# LB_BIT_2IN_1OUT-LARGE-v03_1_1x.net
KiCad netlist of a schematic drawn in EAGLE
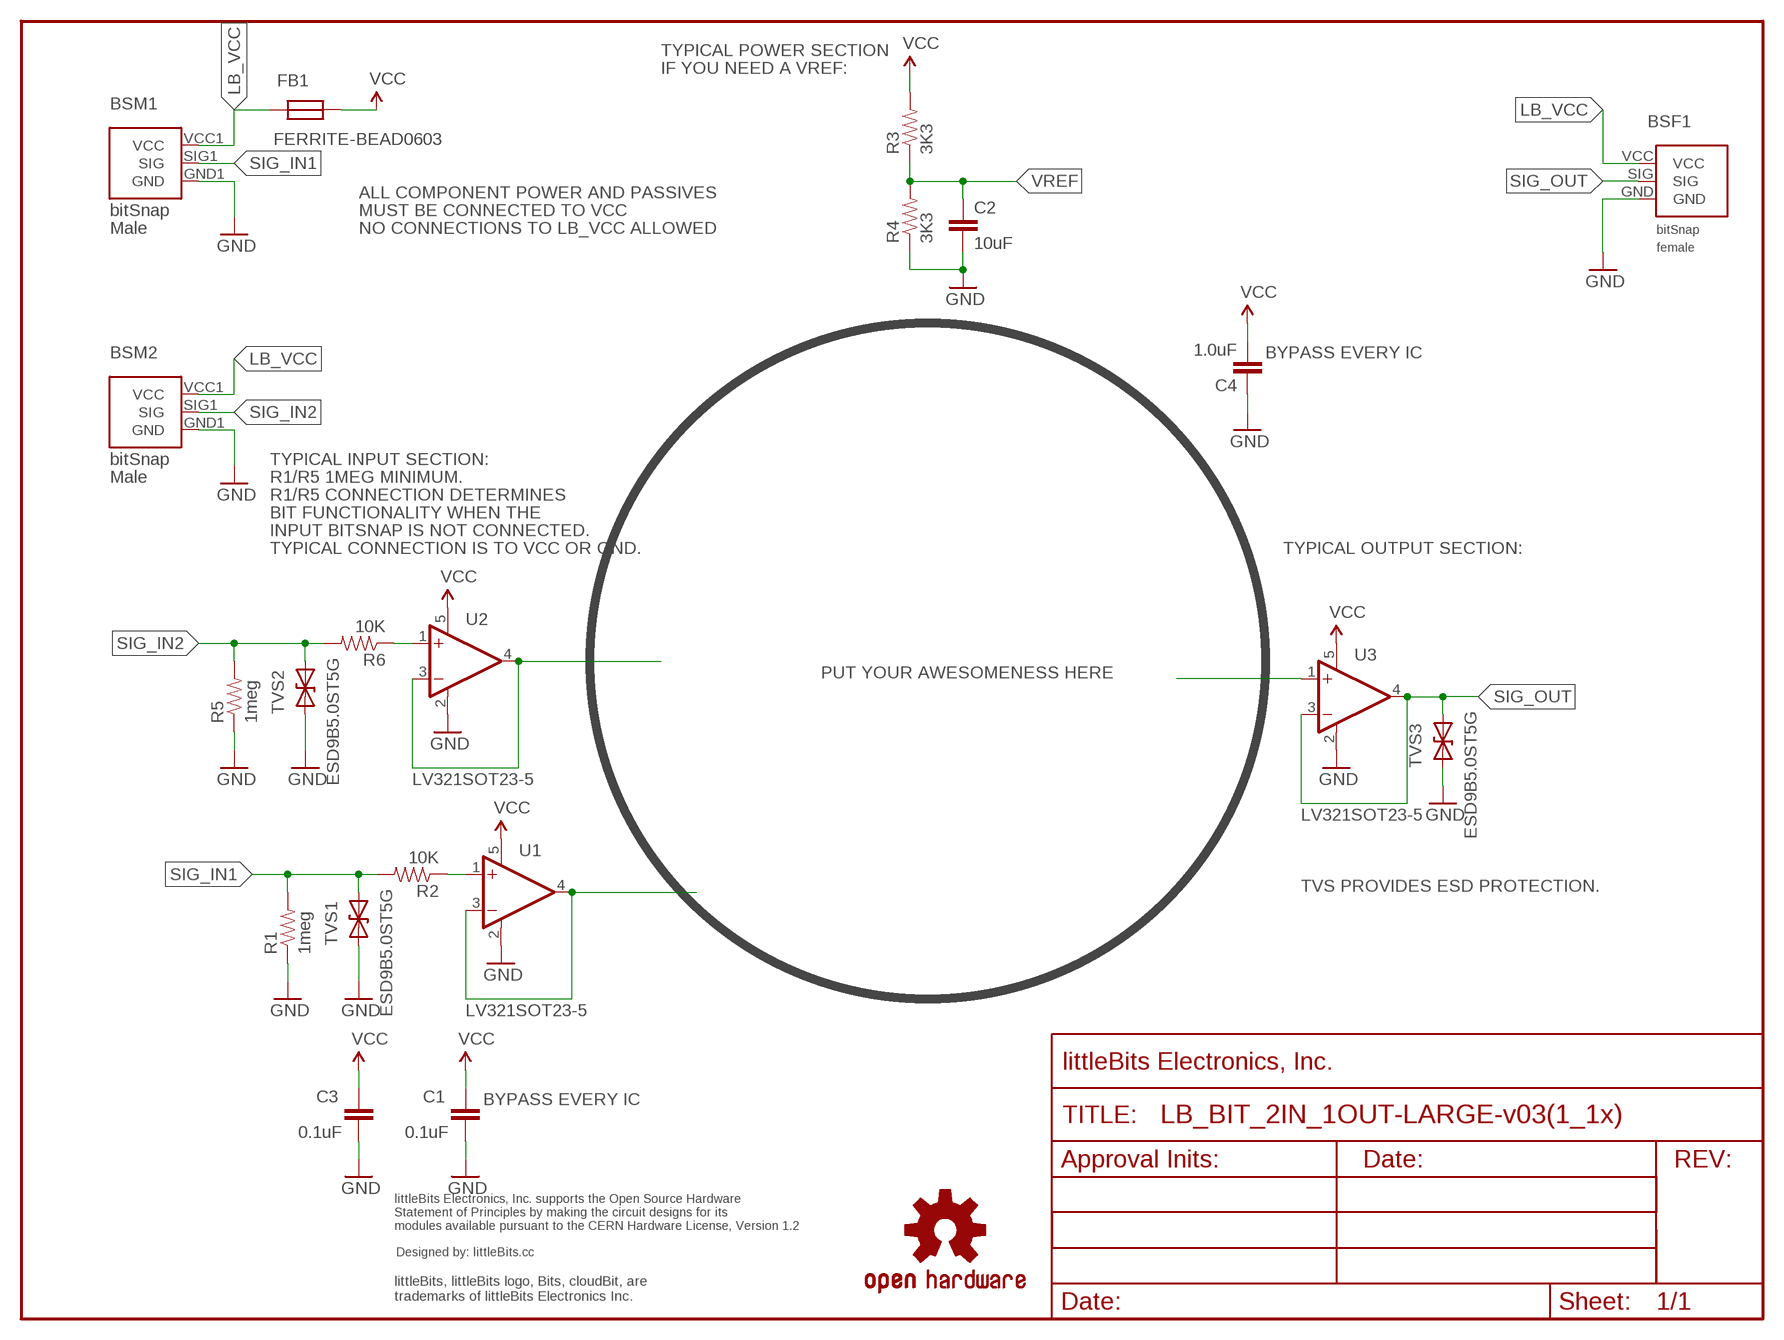
[diagram p0: schematic, sheet 1]

(export (version "E")
  (design (tool "Eeschema 10.0.6"))
  (components
    (comp (ref "BSF1")
      (value "BITSNAP_V03_FEMALE")
      (footprint "eagle-import:BITSNAP_V03_FEMALE")
      (libsource (lib "eagle-import") (part "BITSNAP_V03_FEMALE"))
    )
    (comp (ref "BSM1")
      (value "BITSNAP_V03_MALE")
      (footprint "eagle-import:BITSNAP_V03_MALE")
      (libsource (lib "eagle-import") (part "BITSNAP_V03_MALE"))
    )
    (comp (ref "BSM2")
      (value "BITSNAP_V03_MALE")
      (footprint "eagle-import:BITSNAP_V03_MALE")
      (libsource (lib "eagle-import") (part "BITSNAP_V03_MALE"))
    )
    (comp (ref "C1")
      (value "0.1uF")
      (footprint "eagle-import:CAP-0603")
      (libsource (lib "eagle-import") (part "CAPCAP-0603"))
    )
    (comp (ref "C2")
      (value "10uF")
      (footprint "eagle-import:CAP-0603")
      (libsource (lib "eagle-import") (part "CAPCAP-0603"))
    )
    (comp (ref "C3")
      (value "0.1uF")
      (footprint "eagle-import:CAP-0603")
      (libsource (lib "eagle-import") (part "CAPCAP-0603"))
    )
    (comp (ref "C4")
      (value "1.0uF")
      (footprint "eagle-import:CAP-0603")
      (libsource (lib "eagle-import") (part "CAPCAP-0603"))
    )
    (comp (ref "FB1")
      (value "FERRITE-BEAD0603")
      (footprint "eagle-import:R0603")
      (libsource (lib "eagle-import") (part "FERRITE-BEAD0603"))
    )
    (comp (ref "FRAME1")
      (value "FRAME-LETTER")
      (footprint "eagle-import:FABDWG01-OHW")
      (libsource (lib "eagle-import") (part "FRAME-LETTER"))
    )
    (comp (ref "R1")
      (value "1meg")
      (footprint "eagle-import:RES-0603")
      (libsource (lib "eagle-import") (part "RESISTOR0603"))
    )
    (comp (ref "R2")
      (value "10K")
      (footprint "eagle-import:RES-0603")
      (libsource (lib "eagle-import") (part "RESISTOR0603"))
    )
    (comp (ref "R3")
      (value "3K3")
      (footprint "eagle-import:RES-0603")
      (libsource (lib "eagle-import") (part "RESISTOR0603"))
    )
    (comp (ref "R4")
      (value "3K3")
      (footprint "eagle-import:RES-0603")
      (libsource (lib "eagle-import") (part "RESISTOR0603"))
    )
    (comp (ref "R5")
      (value "1meg")
      (footprint "eagle-import:RES-0603")
      (libsource (lib "eagle-import") (part "RESISTOR0603"))
    )
    (comp (ref "R6")
      (value "10K")
      (footprint "eagle-import:RES-0603")
      (libsource (lib "eagle-import") (part "RESISTOR0603"))
    )
    (comp (ref "TVS1")
      (value "ESD9B5.0ST5G")
      (footprint "eagle-import:SOD-923")
      (libsource (lib "eagle-import") (part "DIODE-TVSSOD-923"))
    )
    (comp (ref "TVS2")
      (value "ESD9B5.0ST5G")
      (footprint "eagle-import:SOD-923")
      (libsource (lib "eagle-import") (part "DIODE-TVSSOD-923"))
    )
    (comp (ref "TVS3")
      (value "ESD9B5.0ST5G")
      (footprint "eagle-import:SOD-923")
      (libsource (lib "eagle-import") (part "DIODE-TVSSOD-923"))
    )
    (comp (ref "U$1")
      (value "OSHWCREDIT")
      (footprint "eagle-import:OSHWCREDIT")
      (libsource (lib "eagle-import") (part "OSHWCREDIT"))
    )
    (comp (ref "U$2")
      (value "OSHW-LOGOL")
      (footprint "eagle-import:OSHW-LOGO-L")
      (libsource (lib "eagle-import") (part "OSHW-LOGOL"))
    )
    (comp (ref "U1")
      (value "LV321SOT23-5")
      (footprint "eagle-import:SOT23-5")
      (libsource (lib "eagle-import") (part "LV321SOT23-5"))
    )
    (comp (ref "U2")
      (value "LV321SOT23-5")
      (footprint "eagle-import:SOT23-5")
      (libsource (lib "eagle-import") (part "LV321SOT23-5"))
    )
    (comp (ref "U3")
      (value "LV321SOT23-5")
      (footprint "eagle-import:SOT23-5")
      (libsource (lib "eagle-import") (part "LV321SOT23-5"))
    )
  )
  (nets
    (net (code "1") (name "GND") (class "Default")
      (node (ref "BSF1") (pin "GND") (pinfunction "GND_GND") (pintype "bidirectional"))
      (node (ref "BSM1") (pin "GND1") (pinfunction "GND_GND1") (pintype "bidirectional"))
      (node (ref "BSM2") (pin "GND1") (pinfunction "GND_GND1") (pintype "bidirectional"))
      (node (ref "C1") (pin "2") (pinfunction "2_2") (pintype "passive"))
      (node (ref "C2") (pin "2") (pinfunction "2_2") (pintype "passive"))
      (node (ref "C3") (pin "2") (pinfunction "2_2") (pintype "passive"))
      (node (ref "C4") (pin "1") (pinfunction "1_1") (pintype "passive"))
      (node (ref "R1") (pin "1") (pinfunction "1_1") (pintype "passive"))
      (node (ref "R4") (pin "1") (pinfunction "1_1") (pintype "passive"))
      (node (ref "R5") (pin "1") (pinfunction "1_1") (pintype "passive"))
      (node (ref "TVS1") (pin "1") (pinfunction "A_1") (pintype "passive"))
      (node (ref "TVS2") (pin "1") (pinfunction "A_1") (pintype "passive"))
      (node (ref "TVS3") (pin "1") (pinfunction "A_1") (pintype "passive"))
      (node (ref "U1") (pin "2") (pinfunction "V-_2") (pintype "power_in"))
      (node (ref "U2") (pin "2") (pinfunction "V-_2") (pintype "power_in"))
      (node (ref "U3") (pin "2") (pinfunction "V-_2") (pintype "power_in"))
    )
    (net (code "2") (name "LB_VCC") (class "Default")
      (node (ref "BSF1") (pin "VCC") (pinfunction "VCC_VCC") (pintype "bidirectional"))
      (node (ref "BSM1") (pin "VCC1") (pinfunction "VCC_VCC1") (pintype "bidirectional"))
      (node (ref "BSM2") (pin "VCC1") (pinfunction "VCC_VCC1") (pintype "bidirectional"))
      (node (ref "FB1") (pin "2") (pinfunction "P$2_2") (pintype "bidirectional"))
    )
    (net (code "3") (name "Net-(U1-+IN)") (class "Default")
      (node (ref "R2") (pin "1") (pinfunction "1_1") (pintype "passive"))
      (node (ref "U1") (pin "1") (pinfunction "+IN_1") (pintype "input"))
    )
    (net (code "4") (name "Net-(U1--IN)") (class "Default")
      (node (ref "U1") (pin "3") (pinfunction "-IN_3") (pintype "input"))
      (node (ref "U1") (pin "4") (pinfunction "OUT_4") (pintype "output"))
    )
    (net (code "5") (name "Net-(U2-+IN)") (class "Default")
      (node (ref "R6") (pin "1") (pinfunction "1_1") (pintype "passive"))
      (node (ref "U2") (pin "1") (pinfunction "+IN_1") (pintype "input"))
    )
    (net (code "6") (name "Net-(U2--IN)") (class "Default")
      (node (ref "U2") (pin "3") (pinfunction "-IN_3") (pintype "input"))
      (node (ref "U2") (pin "4") (pinfunction "OUT_4") (pintype "output"))
    )
    (net (code "7") (name "SIG_IN1") (class "Default")
      (node (ref "BSM1") (pin "SIG1") (pinfunction "SIG_SIG1") (pintype "bidirectional"))
      (node (ref "R1") (pin "2") (pinfunction "2_2") (pintype "passive"))
      (node (ref "R2") (pin "2") (pinfunction "2_2") (pintype "passive"))
      (node (ref "TVS1") (pin "2") (pinfunction "C_2") (pintype "passive"))
    )
    (net (code "8") (name "SIG_IN2") (class "Default")
      (node (ref "BSM2") (pin "SIG1") (pinfunction "SIG_SIG1") (pintype "bidirectional"))
      (node (ref "R5") (pin "2") (pinfunction "2_2") (pintype "passive"))
      (node (ref "R6") (pin "2") (pinfunction "2_2") (pintype "passive"))
      (node (ref "TVS2") (pin "2") (pinfunction "C_2") (pintype "passive"))
    )
    (net (code "9") (name "SIG_OUT") (class "Default")
      (node (ref "BSF1") (pin "SIG") (pinfunction "SIG_SIG") (pintype "bidirectional"))
      (node (ref "TVS3") (pin "2") (pinfunction "C_2") (pintype "passive"))
      (node (ref "U3") (pin "3") (pinfunction "-IN_3") (pintype "input"))
      (node (ref "U3") (pin "4") (pinfunction "OUT_4") (pintype "output"))
    )
    (net (code "10") (name "VCC") (class "Default")
      (node (ref "C1") (pin "1") (pinfunction "1_1") (pintype "passive"))
      (node (ref "C3") (pin "1") (pinfunction "1_1") (pintype "passive"))
      (node (ref "C4") (pin "2") (pinfunction "2_2") (pintype "passive"))
      (node (ref "FB1") (pin "1") (pinfunction "P$1_1") (pintype "bidirectional"))
      (node (ref "R3") (pin "2") (pinfunction "2_2") (pintype "passive"))
      (node (ref "U1") (pin "5") (pinfunction "V+_5") (pintype "power_in"))
      (node (ref "U2") (pin "5") (pinfunction "V+_5") (pintype "power_in"))
      (node (ref "U3") (pin "5") (pinfunction "V+_5") (pintype "power_in"))
    )
    (net (code "11") (name "VREF") (class "Default")
      (node (ref "C2") (pin "1") (pinfunction "1_1") (pintype "passive"))
      (node (ref "R3") (pin "1") (pinfunction "1_1") (pintype "passive"))
      (node (ref "R4") (pin "2") (pinfunction "2_2") (pintype "passive"))
    )
    (net (code "12") (name "unconnected-(U3-+IN-Pad1)") (class "Default")
      (node (ref "U3") (pin "1") (pinfunction "+IN_1") (pintype "input"))
    )
  )
)
